# OSO-SWAT-A1-05-BLUE.net
KiCad netlist of a schematic drawn in EAGLE
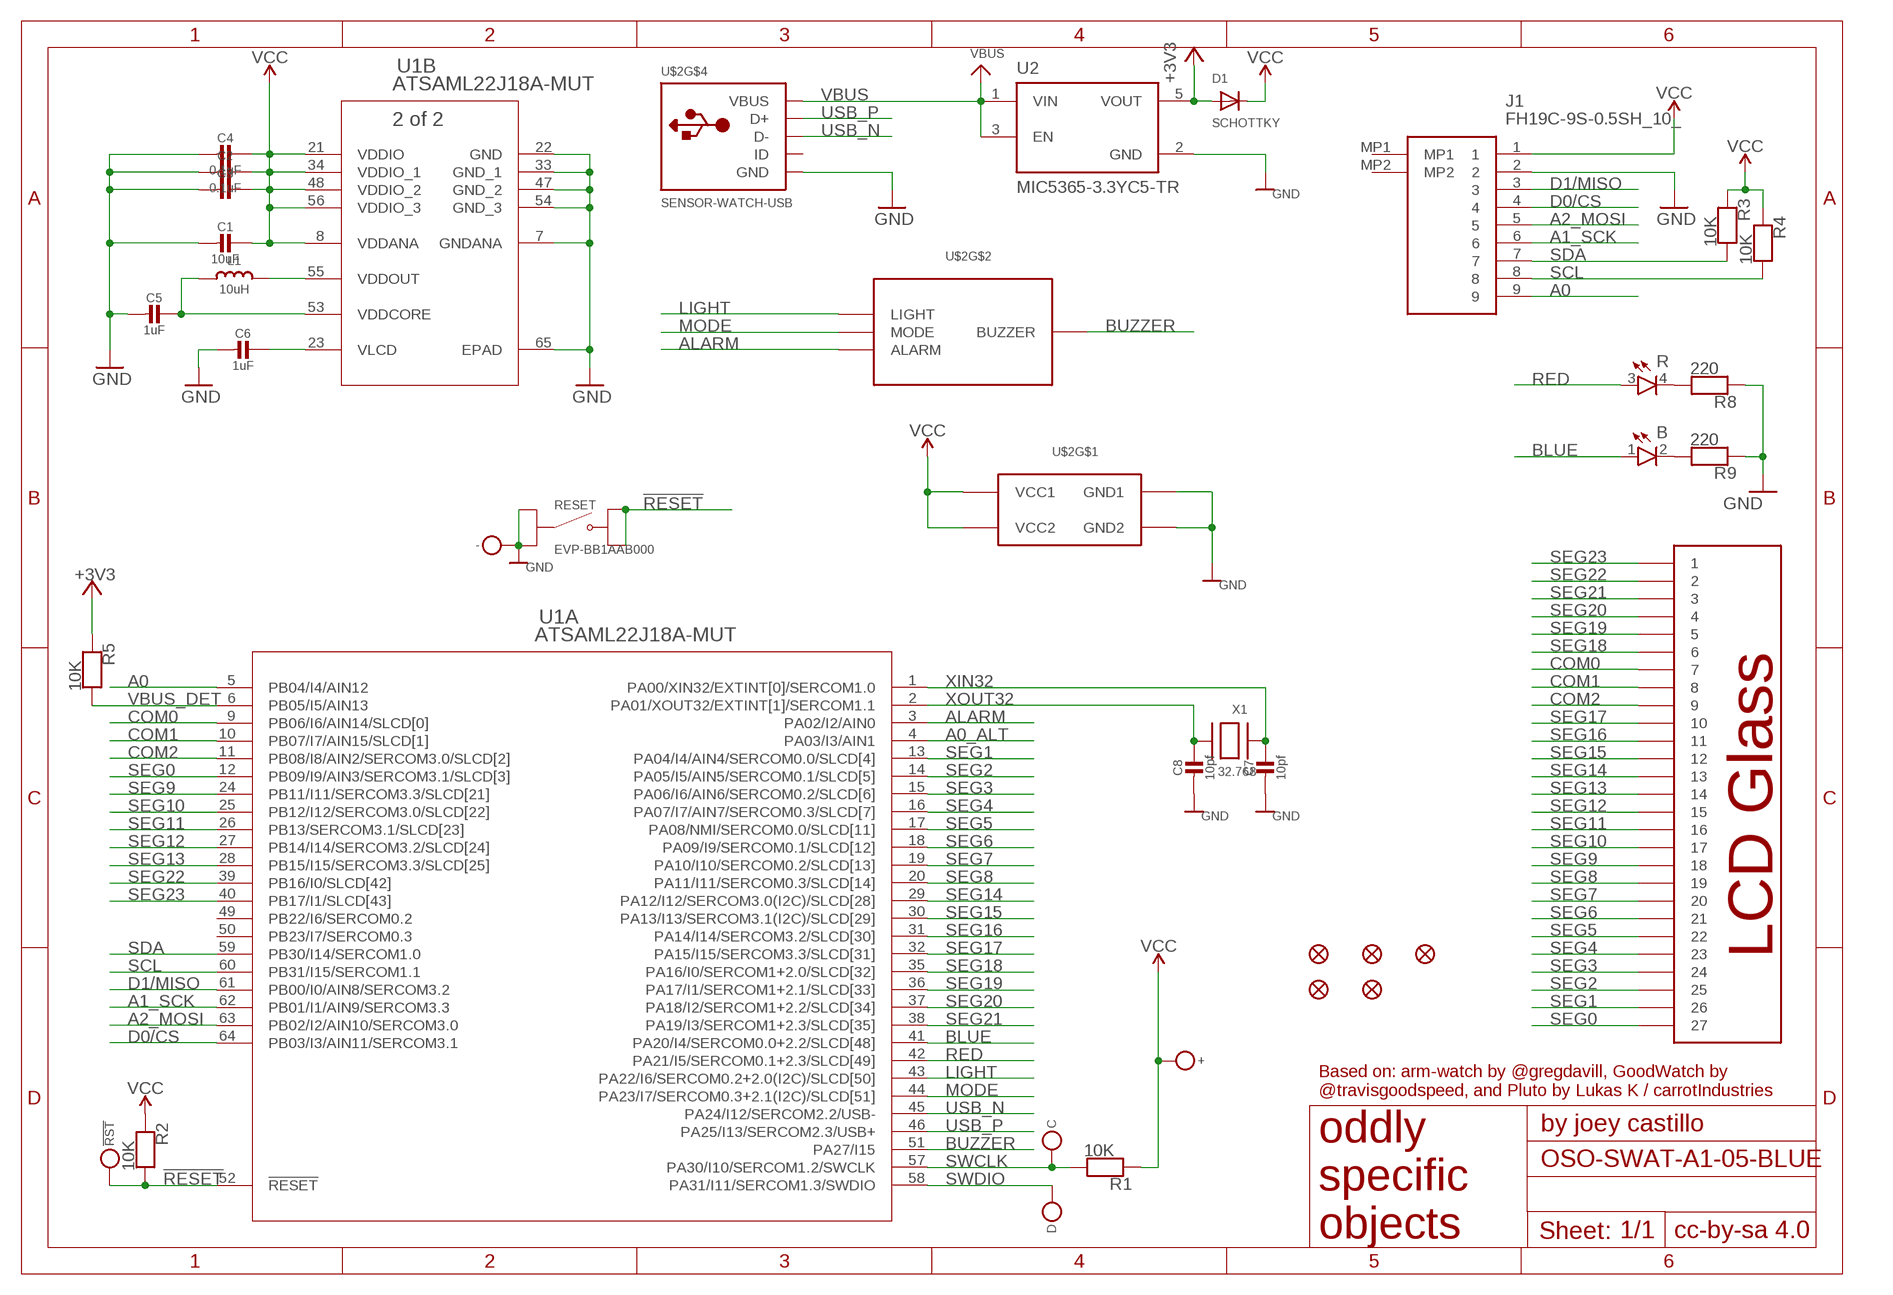
[diagram p0: schematic, sheet 1]

(export (version "E")
  (design (tool "Eeschema 10.0.6"))
  (components
    (comp (ref "!RST")
      (value "MICROBUILDER_TESTPOINTROUND1.5MM")
      (footprint "eagle-import:MICROBUILDER_TESTPOINT_ROUND_1.5MM")
      (libsource (lib "eagle-import") (part "MICROBUILDER_TESTPOINTROUND1.5MM"))
    )
    (comp (ref "+")
      (value "MICROBUILDER_TESTPOINTROUND1.5MM")
      (footprint "eagle-import:MICROBUILDER_TESTPOINT_ROUND_1.5MM")
      (libsource (lib "eagle-import") (part "MICROBUILDER_TESTPOINTROUND1.5MM"))
    )
    (comp (ref "-")
      (value "MICROBUILDER_TESTPOINTROUND1.5MM")
      (footprint "eagle-import:MICROBUILDER_TESTPOINT_ROUND_1.5MM")
      (libsource (lib "eagle-import") (part "MICROBUILDER_TESTPOINTROUND1.5MM"))
    )
    (comp (ref "C")
      (value "MICROBUILDER_TESTPOINTROUND1.5MM")
      (footprint "eagle-import:MICROBUILDER_TESTPOINT_ROUND_1.5MM")
      (libsource (lib "eagle-import") (part "MICROBUILDER_TESTPOINTROUND1.5MM"))
    )
    (comp (ref "C1")
      (value "10uF")
      (footprint "eagle-import:_0603MP")
      (libsource (lib "eagle-import") (part "CAP_CERAMIC_0603MP"))
    )
    (comp (ref "C2")
      (value "0.1uF")
      (footprint "eagle-import:_0603MP")
      (libsource (lib "eagle-import") (part "CAP_CERAMIC_0603MP"))
    )
    (comp (ref "C3")
      (value "0.1uF")
      (footprint "eagle-import:_0603MP")
      (libsource (lib "eagle-import") (part "CAP_CERAMIC_0603MP"))
    )
    (comp (ref "C4")
      (value "0.1uF")
      (footprint "eagle-import:_0603MP")
      (libsource (lib "eagle-import") (part "CAP_CERAMIC_0603MP"))
    )
    (comp (ref "C5")
      (value "1uF")
      (footprint "eagle-import:_0603MP")
      (libsource (lib "eagle-import") (part "CAP_CERAMIC_0603MP"))
    )
    (comp (ref "C6")
      (value "1uF")
      (footprint "eagle-import:_0603MP")
      (libsource (lib "eagle-import") (part "CAP_CERAMIC_0603MP"))
    )
    (comp (ref "C7")
      (value "10pf")
      (footprint "eagle-import:_0402MP")
      (libsource (lib "eagle-import") (part "CAP_CERAMIC_0402MP"))
    )
    (comp (ref "C8")
      (value "10pf")
      (footprint "eagle-import:_0402MP")
      (libsource (lib "eagle-import") (part "CAP_CERAMIC_0402MP"))
    )
    (comp (ref "D")
      (value "MICROBUILDER_TESTPOINTROUND1.5MM")
      (footprint "eagle-import:MICROBUILDER_TESTPOINT_ROUND_1.5MM")
      (libsource (lib "eagle-import") (part "MICROBUILDER_TESTPOINTROUND1.5MM"))
    )
    (comp (ref "D1")
      (value "SCHOTTKY")
      (footprint "eagle-import:SOD-323F")
      (libsource (lib "eagle-import") (part "DIODESOD-323F"))
    )
    (comp (ref "FID1")
      (value "FIDUCIAL_1MM")
      (footprint "eagle-import:FIDUCIAL_1MM")
      (libsource (lib "eagle-import") (part "FIDUCIAL_1MM"))
    )
    (comp (ref "FID2")
      (value "FIDUCIAL_1MM")
      (footprint "eagle-import:FIDUCIAL_1MM")
      (libsource (lib "eagle-import") (part "FIDUCIAL_1MM"))
    )
    (comp (ref "FID3")
      (value "FIDUCIAL_1MM")
      (footprint "eagle-import:FIDUCIAL_1MM")
      (fields (field (name "REV") "A"))
      (libsource (lib "eagle-import") (part "FIDUCIAL_1MM"))
    )
    (comp (ref "FID4")
      (value "FIDUCIAL_1MM")
      (footprint "eagle-import:FIDUCIAL_1MM")
      (libsource (lib "eagle-import") (part "FIDUCIAL_1MM"))
    )
    (comp (ref "FID6")
      (value "FIDUCIAL_1MM")
      (footprint "eagle-import:FIDUCIAL_1MM")
      (fields (field (name "REV") "A"))
      (libsource (lib "eagle-import") (part "FIDUCIAL_1MM"))
    )
    (comp (ref "J1")
      (value "FH19C-9S-0.5SH_10_")
      (footprint "eagle-import:FH19C9S05SH10")
      (fields
        (field (name "MANUFACTURER_PART_NUMBER") "FH19C-9S-0.5SH(10)")
        (field (name "MOUSER_PART_NUMBER") "798-FH19C9S05SH10")
      )
      (libsource (lib "eagle-import") (part "FH19C-9S-0.5SH_10_"))
    )
    (comp (ref "L1")
      (value "10uH")
      (footprint "eagle-import:MICROBUILDER__0805MP")
      (libsource (lib "eagle-import") (part "MICROBUILDER_INDUCTOR_0805MP"))
    )
    (comp (ref "LED")
      (value "QBLP655-RIB")
      (footprint "eagle-import:LED_QBLP655")
      (fields
        (field (name "DIGI-KEY_PART_NUMBER") "160-2026-1-ND")
        (field (name "MF") "Lite-On Inc.")
        (field (name "MP") "LTST-C235KGKRKT")
      )
      (libsource (lib "eagle-import") (part "QBLP655-RIB"))
    )
    (comp (ref "R1")
      (value "10K")
      (footprint "eagle-import:_0603MP")
      (libsource (lib "eagle-import") (part "RESISTOR_0603MP"))
    )
    (comp (ref "R2")
      (value "10K")
      (footprint "eagle-import:_0603MP")
      (libsource (lib "eagle-import") (part "RESISTOR_0603MP"))
    )
    (comp (ref "R3")
      (value "10K")
      (footprint "eagle-import:_0603MP")
      (libsource (lib "eagle-import") (part "RESISTOR_0603MP"))
    )
    (comp (ref "R4")
      (value "10K")
      (footprint "eagle-import:_0603MP")
      (libsource (lib "eagle-import") (part "RESISTOR_0603MP"))
    )
    (comp (ref "R5")
      (value "10K")
      (footprint "eagle-import:_0603MP")
      (libsource (lib "eagle-import") (part "RESISTOR_0603MP"))
    )
    (comp (ref "R8")
      (value "220")
      (footprint "eagle-import:_0603MP")
      (libsource (lib "eagle-import") (part "RESISTOR_0603MP"))
    )
    (comp (ref "R9")
      (value "220")
      (footprint "eagle-import:_0603MP")
      (libsource (lib "eagle-import") (part "RESISTOR_0603MP"))
    )
    (comp (ref "RESET")
      (value "EVP-BB1AAB000")
      (footprint "eagle-import:SW_EVP-BB1AAB000")
      (fields
        (field (name "DIGI-KEY_PART_NUMBER") "P124390CT-ND")
        (field (name "MF") "Panasonic Electronic Components")
      )
      (libsource (lib "eagle-import") (part "EVP-BB1AAB000"))
    )
    (comp (ref "U$2")
      (value "SENSOR-WATCH-USB")
      (footprint "eagle-import:CASIO-F91W-OUTLINE-USB")
      (libsource (lib "eagle-import") (part "SENSOR-WATCH-USB"))
    )
    (comp (ref "U1")
      (value "ATSAML22J18A-MUT")
      (footprint "eagle-import:QFN64_9X9MC_MCH")
      (fields (field (name "COPYRIGHT") "Copyright (C) 2018 Accelerated Designs. All rights reserved"))
      (libsource (lib "eagle-import") (part "ATSAML22J18A-MUT"))
    )
    (comp (ref "U2")
      (value "MIC5365-3.3YC5-TR")
      (footprint "eagle-import:SOT65P210X110-5N")
      (fields (field (name "DIGI-KEY_PART_NUMBER") "576-3193-1-ND") (field (name "MF") "Microchip"))
      (libsource (lib "eagle-import") (part "MIC5365-3.3YC5-TR"))
    )
    (comp (ref "X1")
      (value "32.768")
      (footprint "eagle-import:XTAL3215")
      (libsource (lib "eagle-import") (part "XTAL-3.2X1.5"))
    )
  )
  (nets
    (net (code "1") (name "+3V3") (class "Default")
      (node (ref "D1") (pin "A") (pinfunction "A_A") (pintype "passive"))
      (node (ref "R5") (pin "1") (pinfunction "1_1") (pintype "passive"))
      (node (ref "U2") (pin "5") (pinfunction "VOUT_5") (pintype "output"))
    )
    (net (code "2") (name "/A0") (class "Default")
      (node (ref "J1") (pin "9") (pinfunction "9_9") (pintype "bidirectional"))
      (node (ref "U1") (pin "5") (pinfunction "PB04/I4/AIN12_5") (pintype "bidirectional"))
    )
    (net (code "3") (name "/A0_ALT") (class "Default")
      (node (ref "U1") (pin "4") (pinfunction "PA03/I3/AIN1_4") (pintype "bidirectional"))
    )
    (net (code "4") (name "/A1_SCK") (class "Default")
      (node (ref "J1") (pin "6") (pinfunction "6_6") (pintype "bidirectional"))
      (node (ref "U1") (pin "62") (pinfunction "PB01/I1/AIN9/SERCOM3.3_62") (pintype "bidirectional"))
    )
    (net (code "5") (name "/A2_MOSI") (class "Default")
      (node (ref "J1") (pin "5") (pinfunction "5_5") (pintype "bidirectional"))
      (node (ref "U1") (pin "63") (pinfunction "PB02/I2/AIN10/SERCOM3.0_63") (pintype "bidirectional"))
    )
    (net (code "6") (name "/ALARM") (class "Default")
      (node (ref "U$2") (pin "ALARM") (pinfunction "ALARM_ALARM") (pintype "bidirectional"))
      (node (ref "U1") (pin "3") (pinfunction "PA02/I2/AIN0_3") (pintype "bidirectional"))
    )
    (net (code "7") (name "/BLUE") (class "Default")
      (node (ref "LED") (pin "1") (pinfunction "A_1") (pintype "passive"))
      (node (ref "U1") (pin "41") (pinfunction "PA20/I4/SERCOM0.0+2.2/SLCD[48]_41") (pintype "bidirectional"))
    )
    (net (code "8") (name "/BUZZER") (class "Default")
      (node (ref "U$2") (pin "BUZZER") (pinfunction "BUZZER_BUZZER") (pintype "bidirectional"))
      (node (ref "U1") (pin "51") (pinfunction "PA27/I15_51") (pintype "bidirectional"))
    )
    (net (code "9") (name "/COM0") (class "Default")
      (node (ref "U$2") (pin "7") (pinfunction "7_7") (pintype "input"))
      (node (ref "U1") (pin "9") (pinfunction "PB06/I6/AIN14/SLCD[0]_9") (pintype "bidirectional"))
    )
    (net (code "10") (name "/COM1") (class "Default")
      (node (ref "U$2") (pin "8") (pinfunction "8_8") (pintype "input"))
      (node (ref "U1") (pin "10") (pinfunction "PB07/I7/AIN15/SLCD[1]_10") (pintype "bidirectional"))
    )
    (net (code "11") (name "/COM2") (class "Default")
      (node (ref "U$2") (pin "9") (pinfunction "9_9") (pintype "input"))
      (node (ref "U1") (pin "11") (pinfunction "PB08/I8/AIN2/SERCOM3.0/SLCD[2]_11") (pintype "bidirectional"))
    )
    (net (code "12") (name "/D0{slash}CS") (class "Default")
      (node (ref "J1") (pin "4") (pinfunction "4_4") (pintype "bidirectional"))
      (node (ref "U1") (pin "64") (pinfunction "PB03/I3/AIN11/SERCOM3.1_64") (pintype "bidirectional"))
    )
    (net (code "13") (name "/D1{slash}MISO") (class "Default")
      (node (ref "J1") (pin "3") (pinfunction "3_3") (pintype "bidirectional"))
      (node (ref "U1") (pin "61") (pinfunction "PB00/I0/AIN8/SERCOM3.2_61") (pintype "bidirectional"))
    )
    (net (code "14") (name "/LIGHT") (class "Default")
      (node (ref "U$2") (pin "LIGHT") (pinfunction "LIGHT_LIGHT") (pintype "bidirectional"))
      (node (ref "U1") (pin "43") (pinfunction "PA22/I6/SERCOM0.2+2.0(I2C)/SLCD[50]_43") (pintype "bidirectional"))
    )
    (net (code "15") (name "/MODE") (class "Default")
      (node (ref "U$2") (pin "MODE") (pinfunction "MODE_MODE") (pintype "bidirectional"))
      (node (ref "U1") (pin "44") (pinfunction "PA23/I7/SERCOM0.3+2.1(I2C)/SLCD[51]_44") (pintype "bidirectional"))
    )
    (net (code "16") (name "/RED") (class "Default")
      (node (ref "LED") (pin "3") (pinfunction "A_3") (pintype "passive"))
      (node (ref "U1") (pin "42") (pinfunction "PA21/I5/SERCOM0.1+2.3/SLCD[49]_42") (pintype "bidirectional"))
    )
    (net (code "17") (name "/SCL") (class "Default")
      (node (ref "J1") (pin "8") (pinfunction "8_8") (pintype "bidirectional"))
      (node (ref "R4") (pin "2") (pinfunction "2_2") (pintype "passive"))
      (node (ref "U1") (pin "60") (pinfunction "PB31/I15/SERCOM1.1_60") (pintype "bidirectional"))
    )
    (net (code "18") (name "/SDA") (class "Default")
      (node (ref "J1") (pin "7") (pinfunction "7_7") (pintype "bidirectional"))
      (node (ref "R3") (pin "2") (pinfunction "2_2") (pintype "passive"))
      (node (ref "U1") (pin "59") (pinfunction "PB30/I14/SERCOM1.0_59") (pintype "bidirectional"))
    )
    (net (code "19") (name "/SEG0") (class "Default")
      (node (ref "U$2") (pin "27") (pinfunction "27_27") (pintype "input"))
      (node (ref "U1") (pin "12") (pinfunction "PB09/I9/AIN3/SERCOM3.1/SLCD[3]_12") (pintype "bidirectional"))
    )
    (net (code "20") (name "/SEG1") (class "Default")
      (node (ref "U$2") (pin "26") (pinfunction "26_26") (pintype "input"))
      (node (ref "U1") (pin "13") (pinfunction "PA04/I4/AIN4/SERCOM0.0/SLCD[4]_13") (pintype "bidirectional"))
    )
    (net (code "21") (name "/SEG2") (class "Default")
      (node (ref "U$2") (pin "25") (pinfunction "25_25") (pintype "input"))
      (node (ref "U1") (pin "14") (pinfunction "PA05/I5/AIN5/SERCOM0.1/SLCD[5]_14") (pintype "bidirectional"))
    )
    (net (code "22") (name "/SEG3") (class "Default")
      (node (ref "U$2") (pin "24") (pinfunction "24_24") (pintype "input"))
      (node (ref "U1") (pin "15") (pinfunction "PA06/I6/AIN6/SERCOM0.2/SLCD[6]_15") (pintype "bidirectional"))
    )
    (net (code "23") (name "/SEG4") (class "Default")
      (node (ref "U$2") (pin "23") (pinfunction "23_23") (pintype "input"))
      (node (ref "U1") (pin "16") (pinfunction "PA07/I7/AIN7/SERCOM0.3/SLCD[7]_16") (pintype "bidirectional"))
    )
    (net (code "24") (name "/SEG5") (class "Default")
      (node (ref "U$2") (pin "22") (pinfunction "22_22") (pintype "input"))
      (node (ref "U1") (pin "17") (pinfunction "PA08/NMI/SERCOM0.0/SLCD[11]_17") (pintype "bidirectional"))
    )
    (net (code "25") (name "/SEG6") (class "Default")
      (node (ref "U$2") (pin "21") (pinfunction "21_21") (pintype "input"))
      (node (ref "U1") (pin "18") (pinfunction "PA09/I9/SERCOM0.1/SLCD[12]_18") (pintype "bidirectional"))
    )
    (net (code "26") (name "/SEG7") (class "Default")
      (node (ref "U$2") (pin "20") (pinfunction "20_20") (pintype "input"))
      (node (ref "U1") (pin "19") (pinfunction "PA10/I10/SERCOM0.2/SLCD[13]_19") (pintype "bidirectional"))
    )
    (net (code "27") (name "/SEG8") (class "Default")
      (node (ref "U$2") (pin "19") (pinfunction "19_19") (pintype "input"))
      (node (ref "U1") (pin "20") (pinfunction "PA11/I11/SERCOM0.3/SLCD[14]_20") (pintype "bidirectional"))
    )
    (net (code "28") (name "/SEG9") (class "Default")
      (node (ref "U$2") (pin "18") (pinfunction "18_18") (pintype "input"))
      (node (ref "U1") (pin "24") (pinfunction "PB11/I11/SERCOM3.3/SLCD[21]_24") (pintype "bidirectional"))
    )
    (net (code "29") (name "/SEG10") (class "Default")
      (node (ref "U$2") (pin "17") (pinfunction "17_17") (pintype "input"))
      (node (ref "U1") (pin "25") (pinfunction "PB12/I12/SERCOM3.0/SLCD[22]_25") (pintype "bidirectional"))
    )
    (net (code "30") (name "/SEG11") (class "Default")
      (node (ref "U$2") (pin "16") (pinfunction "16_16") (pintype "input"))
      (node (ref "U1") (pin "26") (pinfunction "PB13/SERCOM3.1/SLCD[23]_26") (pintype "bidirectional"))
    )
    (net (code "31") (name "/SEG12") (class "Default")
      (node (ref "U$2") (pin "15") (pinfunction "15_15") (pintype "input"))
      (node (ref "U1") (pin "27") (pinfunction "PB14/I14/SERCOM3.2/SLCD[24]_27") (pintype "bidirectional"))
    )
    (net (code "32") (name "/SEG13") (class "Default")
      (node (ref "U$2") (pin "14") (pinfunction "14_14") (pintype "input"))
      (node (ref "U1") (pin "28") (pinfunction "PB15/I15/SERCOM3.3/SLCD[25]_28") (pintype "bidirectional"))
    )
    (net (code "33") (name "/SEG14") (class "Default")
      (node (ref "U$2") (pin "13") (pinfunction "13_13") (pintype "input"))
      (node (ref "U1") (pin "29") (pinfunction "PA12/I12/SERCOM3.0(I2C)/SLCD[28]_29") (pintype "bidirectional"))
    )
    (net (code "34") (name "/SEG15") (class "Default")
      (node (ref "U$2") (pin "12") (pinfunction "12_12") (pintype "input"))
      (node (ref "U1") (pin "30") (pinfunction "PA13/I13/SERCOM3.1(I2C)/SLCD[29]_30") (pintype "bidirectional"))
    )
    (net (code "35") (name "/SEG16") (class "Default")
      (node (ref "U$2") (pin "11") (pinfunction "11_11") (pintype "input"))
      (node (ref "U1") (pin "31") (pinfunction "PA14/I14/SERCOM3.2/SLCD[30]_31") (pintype "bidirectional"))
    )
    (net (code "36") (name "/SEG17") (class "Default")
      (node (ref "U$2") (pin "10") (pinfunction "10_10") (pintype "input"))
      (node (ref "U1") (pin "32") (pinfunction "PA15/I15/SERCOM3.3/SLCD[31]_32") (pintype "bidirectional"))
    )
    (net (code "37") (name "/SEG18") (class "Default")
      (node (ref "U$2") (pin "6") (pinfunction "6_6") (pintype "input"))
      (node (ref "U1") (pin "35") (pinfunction "PA16/I0/SERCOM1+2.0/SLCD[32]_35") (pintype "bidirectional"))
    )
    (net (code "38") (name "/SEG19") (class "Default")
      (node (ref "U$2") (pin "5") (pinfunction "5_5") (pintype "input"))
      (node (ref "U1") (pin "36") (pinfunction "PA17/I1/SERCOM1+2.1/SLCD[33]_36") (pintype "bidirectional"))
    )
    (net (code "39") (name "/SEG20") (class "Default")
      (node (ref "U$2") (pin "4") (pinfunction "4_4") (pintype "input"))
      (node (ref "U1") (pin "37") (pinfunction "PA18/I2/SERCOM1+2.2/SLCD[34]_37") (pintype "bidirectional"))
    )
    (net (code "40") (name "/SEG21") (class "Default")
      (node (ref "U$2") (pin "3") (pinfunction "3_3") (pintype "input"))
      (node (ref "U1") (pin "38") (pinfunction "PA19/I3/SERCOM1+2.3/SLCD[35]_38") (pintype "bidirectional"))
    )
    (net (code "41") (name "/SEG22") (class "Default")
      (node (ref "U$2") (pin "2") (pinfunction "2_2") (pintype "input"))
      (node (ref "U1") (pin "39") (pinfunction "PB16/I0/SLCD[42]_39") (pintype "bidirectional"))
    )
    (net (code "42") (name "/SEG23") (class "Default")
      (node (ref "U$2") (pin "1") (pinfunction "1_1") (pintype "input"))
      (node (ref "U1") (pin "40") (pinfunction "PB17/I1/SLCD[43]_40") (pintype "bidirectional"))
    )
    (net (code "43") (name "/SWCLK") (class "Default")
      (node (ref "C") (pin "P$1") (pinfunction "P$1_P$1") (pintype "bidirectional"))
      (node (ref "R1") (pin "2") (pinfunction "2_2") (pintype "passive"))
      (node (ref "U1") (pin "57") (pinfunction "PA30/I10/SERCOM1.2/SWCLK_57") (pintype "bidirectional"))
    )
    (net (code "44") (name "/SWDIO") (class "Default")
      (node (ref "D") (pin "P$1") (pinfunction "P$1_P$1") (pintype "bidirectional"))
      (node (ref "U1") (pin "58") (pinfunction "PA31/I11/SERCOM1.3/SWDIO_58") (pintype "bidirectional"))
    )
    (net (code "45") (name "/USB_N") (class "Default")
      (node (ref "U$2") (pin "USB_N") (pinfunction "D-_USB_N") (pintype "bidirectional"))
      (node (ref "U1") (pin "45") (pinfunction "PA24/I12/SERCOM2.2/USB-_45") (pintype "bidirectional"))
    )
    (net (code "46") (name "/USB_P") (class "Default")
      (node (ref "U$2") (pin "USB_P") (pinfunction "D+_USB_P") (pintype "bidirectional"))
      (node (ref "U1") (pin "46") (pinfunction "PA25/I13/SERCOM2.3/USB+_46") (pintype "bidirectional"))
    )
    (net (code "47") (name "/VBUS_DET") (class "Default")
      (node (ref "R5") (pin "2") (pinfunction "2_2") (pintype "passive"))
      (node (ref "U1") (pin "6") (pinfunction "PB05/I5/AIN13_6") (pintype "bidirectional"))
    )
    (net (code "48") (name "/XIN32") (class "Default")
      (node (ref "C7") (pin "1") (pinfunction "1_1") (pintype "passive"))
      (node (ref "U1") (pin "1") (pinfunction "PA00/XIN32/EXTINT[0]/SERCOM1.0_1") (pintype "bidirectional"))
      (node (ref "X1") (pin "P$1") (pinfunction "P$1_P$1") (pintype "bidirectional"))
    )
    (net (code "49") (name "/XOUT32") (class "Default")
      (node (ref "C8") (pin "1") (pinfunction "1_1") (pintype "passive"))
      (node (ref "U1") (pin "2") (pinfunction "PA01/XOUT32/EXTINT[1]/SERCOM1.1_2") (pintype "bidirectional"))
      (node (ref "X1") (pin "P$2") (pinfunction "P$2_P$2") (pintype "bidirectional"))
    )
    (net (code "50") (name "/~{RESET}") (class "Default")
      (node (ref "!RST") (pin "P$1") (pinfunction "P$1_P$1") (pintype "bidirectional"))
      (node (ref "R2") (pin "2") (pinfunction "2_2") (pintype "passive"))
      (node (ref "RESET") (pin "B1") (pinfunction "B1_B1") (pintype "passive"))
      (node (ref "RESET") (pin "B2") (pinfunction "B2_B2") (pintype "passive"))
      (node (ref "U1") (pin "52") (pinfunction "~{RESET}_52") (pintype "bidirectional"))
    )
    (net (code "51") (name "GND") (class "Default")
      (node (ref "-") (pin "P$1") (pinfunction "P$1_P$1") (pintype "bidirectional"))
      (node (ref "C1") (pin "2") (pinfunction "2_2") (pintype "passive"))
      (node (ref "C2") (pin "2") (pinfunction "2_2") (pintype "passive"))
      (node (ref "C3") (pin "2") (pinfunction "2_2") (pintype "passive"))
      (node (ref "C4") (pin "2") (pinfunction "2_2") (pintype "passive"))
      (node (ref "C5") (pin "2") (pinfunction "2_2") (pintype "passive"))
      (node (ref "C6") (pin "2") (pinfunction "2_2") (pintype "passive"))
      (node (ref "C7") (pin "2") (pinfunction "2_2") (pintype "passive"))
      (node (ref "C8") (pin "2") (pinfunction "2_2") (pintype "passive"))
      (node (ref "J1") (pin "2") (pinfunction "2_2") (pintype "bidirectional"))
      (node (ref "R8") (pin "1") (pinfunction "1_1") (pintype "passive"))
      (node (ref "R9") (pin "1") (pinfunction "1_1") (pintype "passive"))
      (node (ref "RESET") (pin "A1") (pinfunction "A1_A1") (pintype "passive"))
      (node (ref "RESET") (pin "A2") (pinfunction "A2_A2") (pintype "passive"))
      (node (ref "U$2") (pin "GND") (pinfunction "GND_GND") (pintype "power_in"))
      (node (ref "U$2") (pin "GND1") (pinfunction "GND1_GND1") (pintype "bidirectional"))
      (node (ref "U$2") (pin "GND2") (pinfunction "GND2_GND2") (pintype "bidirectional"))
      (node (ref "U1") (pin "22") (pinfunction "GND_22") (pintype "passive"))
      (node (ref "U1") (pin "33") (pinfunction "GND_1_33") (pintype "passive"))
      (node (ref "U1") (pin "47") (pinfunction "GND_2_47") (pintype "passive"))
      (node (ref "U1") (pin "54") (pinfunction "GND_3_54") (pintype "passive"))
      (node (ref "U1") (pin "65") (pinfunction "EPAD_65") (pintype "passive"))
      (node (ref "U1") (pin "7") (pinfunction "GNDANA_7") (pintype "passive"))
      (node (ref "U2") (pin "2") (pinfunction "GND_2") (pintype "power_in"))
    )
    (net (code "52") (name "Net-(LEDA-C)") (class "Default")
      (node (ref "LED") (pin "2") (pinfunction "C_2") (pintype "passive"))
      (node (ref "R9") (pin "2") (pinfunction "2_2") (pintype "passive"))
    )
    (net (code "53") (name "Net-(LEDB-C)") (class "Default")
      (node (ref "LED") (pin "4") (pinfunction "C_4") (pintype "passive"))
      (node (ref "R8") (pin "2") (pinfunction "2_2") (pintype "passive"))
    )
    (net (code "54") (name "Net-(U1B-VDDCORE)") (class "Default")
      (node (ref "C5") (pin "1") (pinfunction "1_1") (pintype "passive"))
      (node (ref "L1") (pin "1") (pinfunction "1_1") (pintype "passive"))
      (node (ref "U1") (pin "53") (pinfunction "VDDCORE_53") (pintype "power_in"))
    )
    (net (code "55") (name "Net-(U1B-VDDOUT)") (class "Default")
      (node (ref "L1") (pin "2") (pinfunction "2_2") (pintype "passive"))
      (node (ref "U1") (pin "55") (pinfunction "VDDOUT_55") (pintype "output"))
    )
    (net (code "56") (name "Net-(U1B-VLCD)") (class "Default")
      (node (ref "C6") (pin "1") (pinfunction "1_1") (pintype "passive"))
      (node (ref "U1") (pin "23") (pinfunction "VLCD_23") (pintype "passive"))
    )
    (net (code "57") (name "VBUS") (class "Default")
      (node (ref "U$2") (pin "VBUS") (pinfunction "VBUS_VBUS") (pintype "power_in"))
      (node (ref "U2") (pin "1") (pinfunction "VIN_1") (pintype "input"))
      (node (ref "U2") (pin "3") (pinfunction "EN_3") (pintype "input"))
    )
    (net (code "58") (name "VCC") (class "Default")
      (node (ref "+") (pin "P$1") (pinfunction "P$1_P$1") (pintype "bidirectional"))
      (node (ref "C1") (pin "1") (pinfunction "1_1") (pintype "passive"))
      (node (ref "C2") (pin "1") (pinfunction "1_1") (pintype "passive"))
      (node (ref "C3") (pin "1") (pinfunction "1_1") (pintype "passive"))
      (node (ref "C4") (pin "1") (pinfunction "1_1") (pintype "passive"))
      (node (ref "D1") (pin "C") (pinfunction "C_C") (pintype "passive"))
      (node (ref "J1") (pin "1") (pinfunction "1_1") (pintype "bidirectional"))
      (node (ref "R1") (pin "1") (pinfunction "1_1") (pintype "passive"))
      (node (ref "R2") (pin "1") (pinfunction "1_1") (pintype "passive"))
      (node (ref "R3") (pin "1") (pinfunction "1_1") (pintype "passive"))
      (node (ref "R4") (pin "1") (pinfunction "1_1") (pintype "passive"))
      (node (ref "U$2") (pin "VCC1") (pinfunction "VCC1_VCC1") (pintype "bidirectional"))
      (node (ref "U$2") (pin "VCC2") (pinfunction "VCC2_VCC2") (pintype "bidirectional"))
      (node (ref "U1") (pin "21") (pinfunction "VDDIO_21") (pintype "power_in"))
      (node (ref "U1") (pin "34") (pinfunction "VDDIO_1_34") (pintype "power_in"))
      (node (ref "U1") (pin "48") (pinfunction "VDDIO_2_48") (pintype "power_in"))
      (node (ref "U1") (pin "56") (pinfunction "VDDIO_3_56") (pintype "power_in"))
      (node (ref "U1") (pin "8") (pinfunction "VDDANA_8") (pintype "power_in"))
    )
    (net (code "59") (name "unconnected-(J1-PadMP1)") (class "Default")
      (node (ref "J1") (pin "MP1") (pinfunction "MP1_MP1") (pintype "bidirectional"))
    )
    (net (code "60") (name "unconnected-(J1-PadMP2)") (class "Default")
      (node (ref "J1") (pin "MP2") (pinfunction "MP2_MP2") (pintype "bidirectional"))
    )
    (net (code "61") (name "unconnected-(U$2D-ID-PadUSB_ID)") (class "Default")
      (node (ref "U$2") (pin "USB_ID") (pinfunction "ID_USB_ID") (pintype "bidirectional"))
    )
    (net (code "62") (name "unconnected-(U1A-PB22{slash}I6{slash}SERCOM0.2-Pad49)") (class "Default")
      (node (ref "U1") (pin "49") (pinfunction "PB22/I6/SERCOM0.2_49") (pintype "bidirectional"))
    )
    (net (code "63") (name "unconnected-(U1A-PB23{slash}I7{slash}SERCOM0.3-Pad50)") (class "Default")
      (node (ref "U1") (pin "50") (pinfunction "PB23/I7/SERCOM0.3_50") (pintype "bidirectional"))
    )
  )
)
